# SCH_Tanbre_v2_2026-05-30_new.net
KiCad netlist of a schematic drawn in EasyEDA
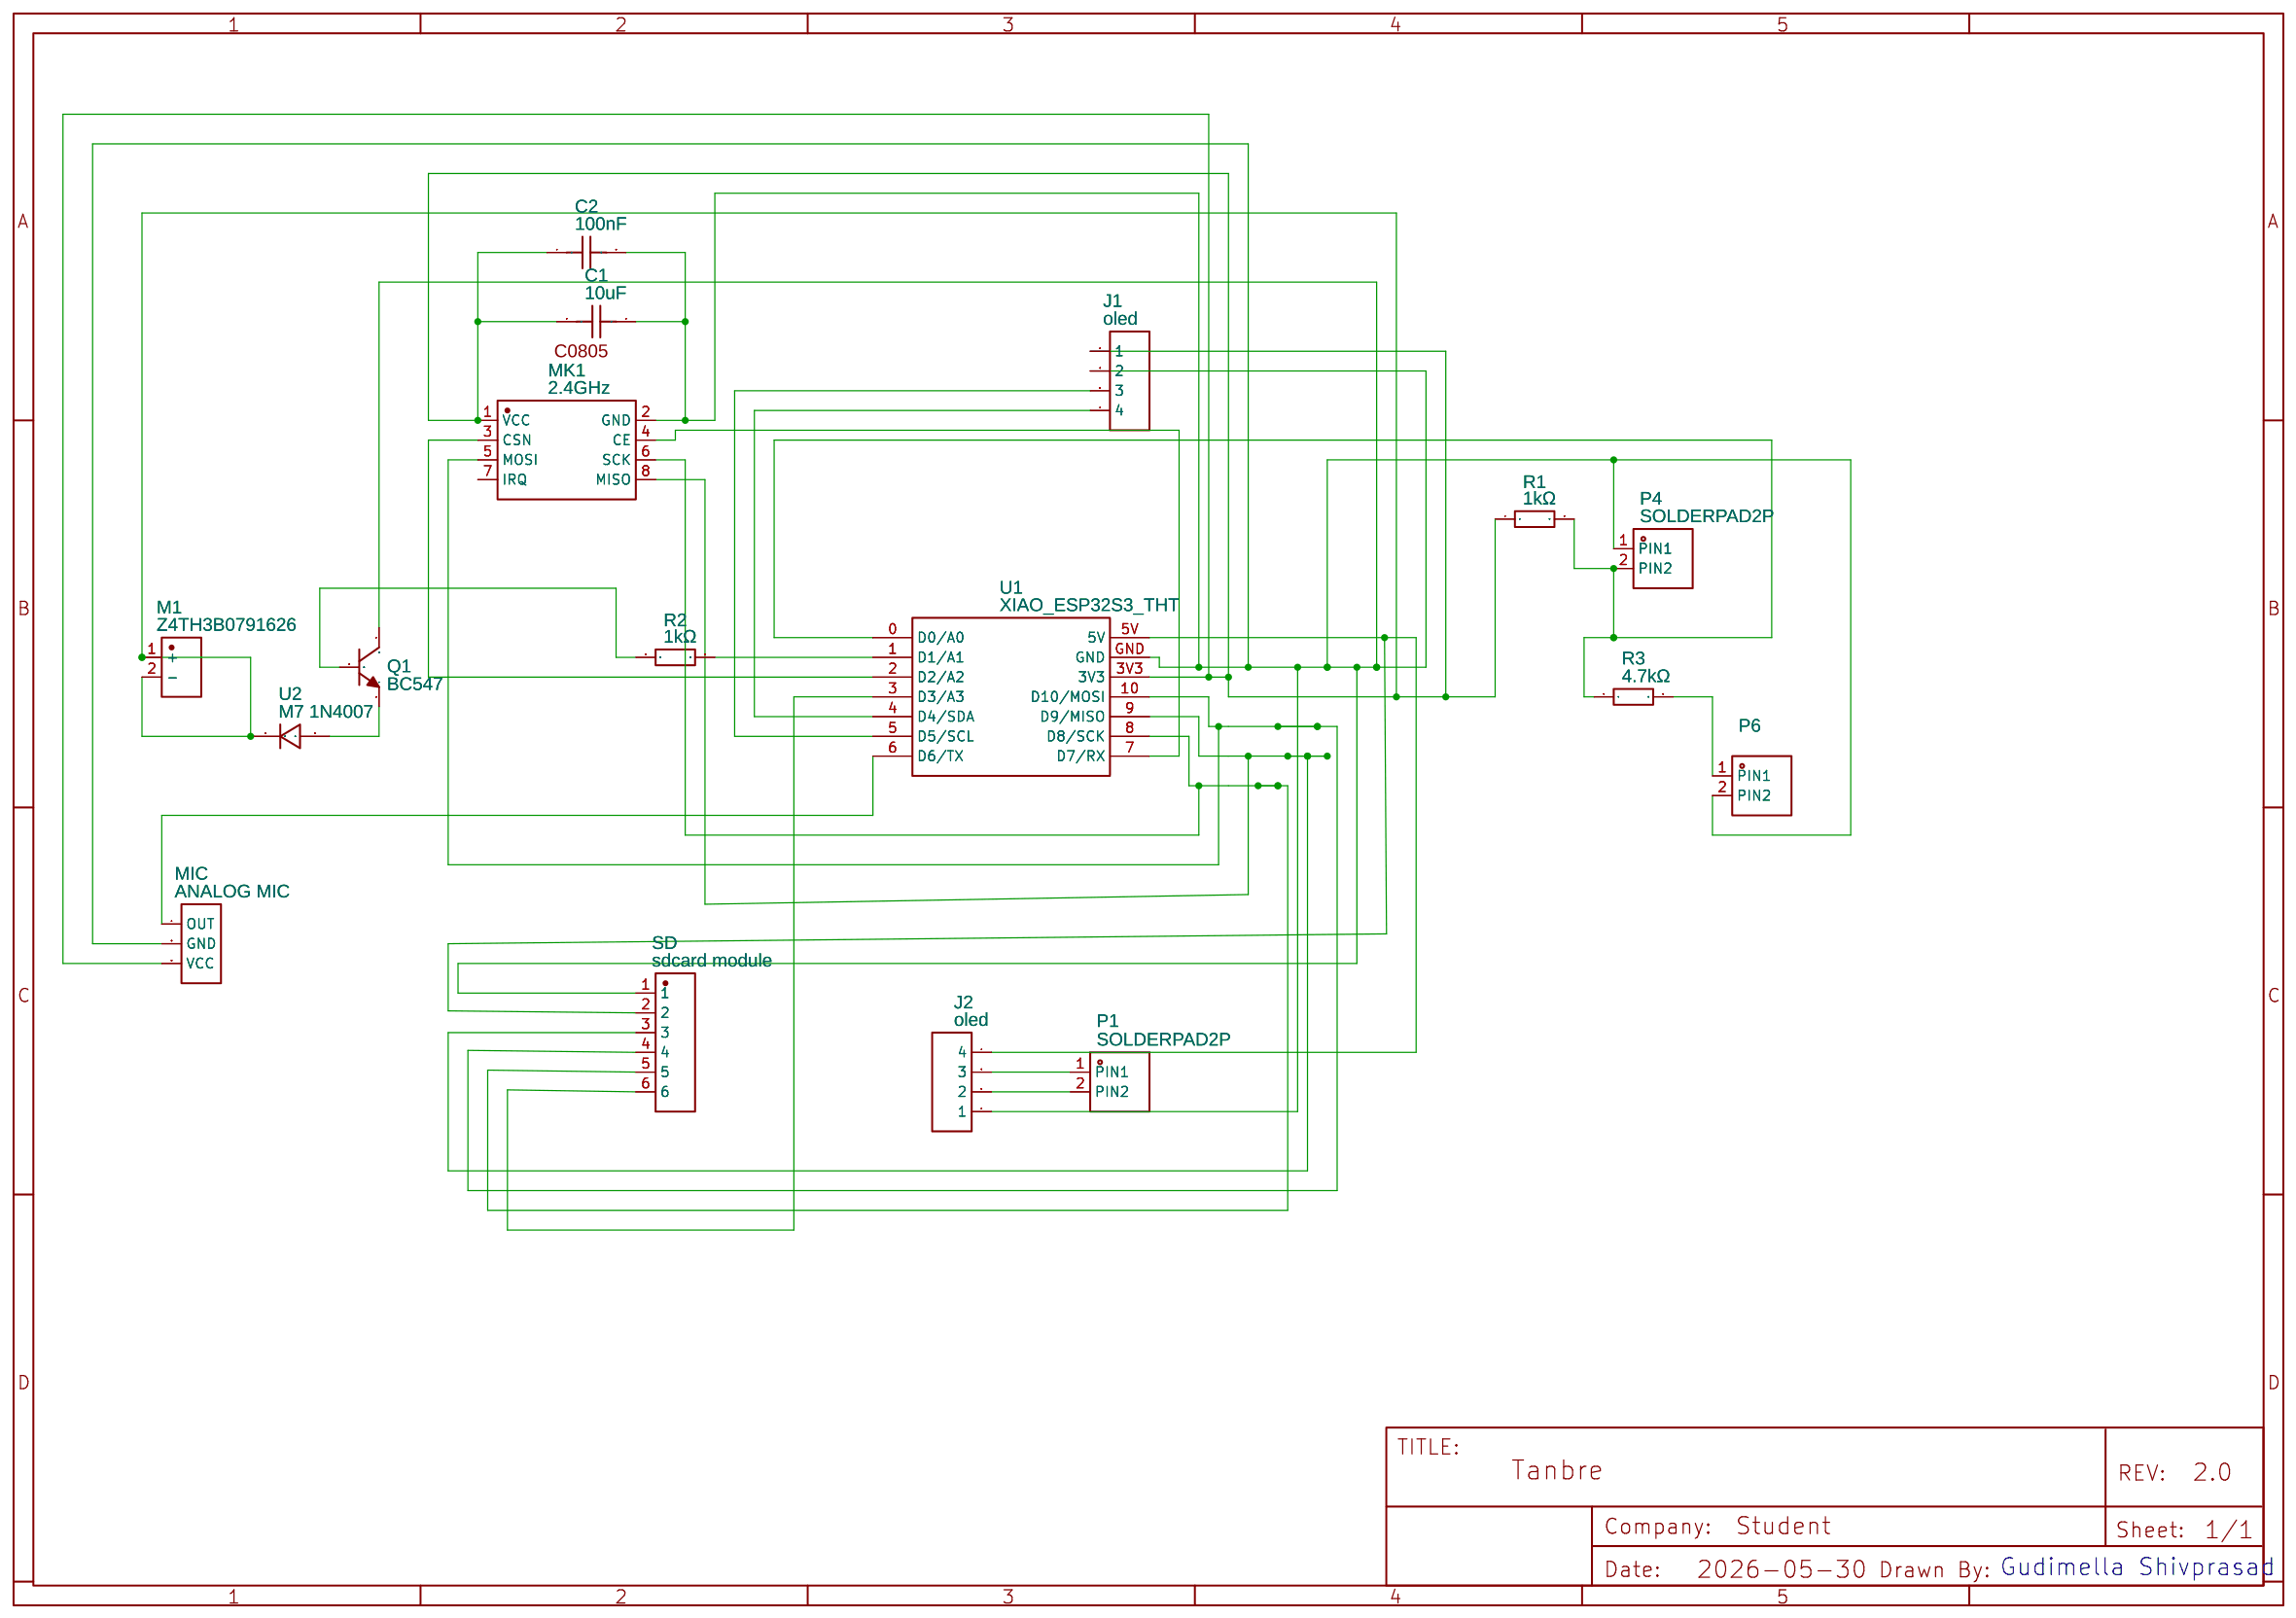
[diagram p0: schematic sheet]

(export (version "E")
  (design (tool "Eeschema 10.0.6"))
  (components
    (comp (ref "C1")
      (value "10uF")
      (fields
        (field (name "Manufacturer Part") "V106K0805X5R250NHP")
        (field (name "Manufacturer") "VIIYONG(微容)")
      )
      (libsource (lib "") (part "V106K0805X5R250NHP"))
    )
    (comp (ref "C2")
      (value "100nF")
      (fields
        (field (name "Manufacturer Part") "VJ0805Y104KXXCW1BC")
        (field (name "Manufacturer") "VISHAY(威世)")
      )
      (libsource (lib "") (part "VJ0805Y104KXXCW1BC"))
    )
    (comp (ref "J1") (value "oled") (libsource (lib "") (part "HDR-M-2.54_1x4")))
    (comp (ref "J2") (value "oled") (libsource (lib "") (part "HDR-M-2.54_1x4_1")))
    (comp (ref "M1")
      (value "Z4TH3B0791626")
      (fields (field (name "Manufacturer") "KOTL(金龙机电)"))
      (libsource (lib "") (part "Z4TH3B0791626"))
    )
    (comp (ref "MIC") (value "ANALOG MIC") (libsource (lib "") (part "HDR-M-2.54_1x3")))
    (comp (ref "MK1")
      (value "2.4GHz")
      (fields (field (name "Manufacturer Part") "NF-04") (field (name "Manufacturer") "Ai-Thinker(安信可)"))
      (libsource (lib "") (part "NRF24L01"))
    )
    (comp (ref "P1")
      (value "SOLDERPAD2P")
      (fields (field (name "Manufacturer Part") "New SchematicLib"))
      (libsource (lib "") (part "SOLDERPAD2P"))
    )
    (comp (ref "P4")
      (value "SOLDERPAD2P")
      (fields (field (name "Manufacturer Part") "New SchematicLib"))
      (libsource (lib "") (part "SOLDERPAD2P"))
    )
    (comp (ref "P6")
      (value "SOLDERPAD2P")
      (fields (field (name "Manufacturer Part") "New SchematicLib"))
      (libsource (lib "") (part "SOLDERPAD2P"))
    )
    (comp (ref "Q1")
      (value "BC547")
      (fields
        (field (name "Manufacturer Part") "BC547(RANGE:420-800)")
        (field (name "Manufacturer") "CJ(江苏长电/长晶)")
      )
      (libsource (lib "") (part "BC547"))
    )
    (comp (ref "R1")
      (value "1kΩ")
      (fields (field (name "Manufacturer Part") "CR-02JL6----1K") (field (name "Manufacturer") "Viking(光颉)"))
      (libsource (lib "") (part "CR-02JL6----1K"))
    )
    (comp (ref "R2")
      (value "1kΩ")
      (fields (field (name "Manufacturer Part") "CR-02JL6----1K") (field (name "Manufacturer") "Viking(光颉)"))
      (libsource (lib "") (part "CR-02JL6----1K"))
    )
    (comp (ref "R3")
      (value "4.7kΩ")
      (fields (field (name "Manufacturer Part") "RMC12064.7K5%N") (field (name "Manufacturer") "Tyohm(幸亚电阻)"))
      (libsource (lib "") (part "RMC12064.7K5%N"))
    )
    (comp (ref "SD")
      (value "sdcard module")
      (fields
        (field (name "Manufacturer Part") "HC-PM254-5.0H-1x6PZ")
        (field (name "Manufacturer") "HC(虹成电子)")
      )
      (libsource (lib "") (part "HC-PM254-5.0H-1X6PZ"))
    )
    (comp (ref "U1") (value "XIAO_ESP32S3_THT") (libsource (lib "") (part "XIAO_ESP32S3_THT")))
    (comp (ref "U2")
      (value "M7 1N4007")
      (fields (field (name "Manufacturer") "JUXING(钜兴)"))
      (libsource (lib "") (part "M7 1N4007"))
    )
  )
  (nets
    (net (code "1") (name "Net-(J2-Pad4)") (class "Default")
      (node (ref "J2") (pin "4") (pinfunction "4_4") (pintype "unspecified"))
      (node (ref "SD") (pin "2") (pinfunction "2_2") (pintype "unspecified"))
      (node (ref "U1") (pin "5V") (pinfunction "5V_5V") (pintype "unspecified"))
    )
    (net (code "2") (name "Net-(M1-+)") (class "Default")
      (node (ref "C1") (pin "1") (pinfunction "1_1") (pintype "unspecified"))
      (node (ref "C2") (pin "1") (pinfunction "1_1") (pintype "unspecified"))
      (node (ref "J1") (pin "1") (pinfunction "1_1") (pintype "unspecified"))
      (node (ref "M1") (pin "1") (pinfunction "+_1") (pintype "unspecified"))
      (node (ref "M1") (pin "2") (pinfunction "-_2") (pintype "unspecified"))
      (node (ref "MIC") (pin "3") (pinfunction "VCC_3") (pintype "unspecified"))
      (node (ref "MK1") (pin "1") (pinfunction "VCC_1") (pintype "unspecified"))
      (node (ref "R1") (pin "1") (pinfunction "1_1") (pintype "unspecified"))
      (node (ref "U1") (pin "3V3") (pinfunction "3V3_3V3") (pintype "unspecified"))
      (node (ref "U2") (pin "1") (pinfunction "1_1") (pintype "unspecified"))
    )
    (net (code "3") (name "Net-(MIC-GND)") (class "Default")
      (node (ref "C1") (pin "2") (pinfunction "2_2") (pintype "unspecified"))
      (node (ref "C2") (pin "2") (pinfunction "2_2") (pintype "unspecified"))
      (node (ref "J1") (pin "2") (pinfunction "2_2") (pintype "unspecified"))
      (node (ref "J2") (pin "1") (pinfunction "1_1") (pintype "unspecified"))
      (node (ref "MIC") (pin "2") (pinfunction "GND_2") (pintype "unspecified"))
      (node (ref "MK1") (pin "2") (pinfunction "GND_2") (pintype "unspecified"))
      (node (ref "P4") (pin "1") (pinfunction "PIN1_1") (pintype "unspecified"))
      (node (ref "P6") (pin "2") (pinfunction "PIN2_2") (pintype "unspecified"))
      (node (ref "Q1") (pin "1") (pinfunction "C_1") (pintype "unspecified"))
      (node (ref "SD") (pin "1") (pinfunction "1_1") (pintype "unspecified"))
      (node (ref "U1") (pin "GND") (pinfunction "GND_GND") (pintype "unspecified"))
    )
    (net (code "4") (name "Net-(MIC-OUT)") (class "Default")
      (node (ref "MIC") (pin "1") (pinfunction "OUT_1") (pintype "unspecified"))
      (node (ref "U1") (pin "6") (pinfunction "D6/TX_6") (pintype "unspecified"))
    )
    (net (code "5") (name "Net-(MK1-CE)") (class "Default")
      (node (ref "MK1") (pin "4") (pinfunction "CE_4") (pintype "unspecified"))
      (node (ref "U1") (pin "7") (pinfunction "D7/RX_7") (pintype "unspecified"))
    )
    (net (code "6") (name "Net-(MK1-CSN)") (class "Default")
      (node (ref "MK1") (pin "3") (pinfunction "CSN_3") (pintype "unspecified"))
      (node (ref "U1") (pin "2") (pinfunction "D2/A2_2") (pintype "unspecified"))
    )
    (net (code "7") (name "Net-(MK1-MISO)") (class "Default")
      (node (ref "MK1") (pin "8") (pinfunction "MISO_8") (pintype "unspecified"))
      (node (ref "SD") (pin "3") (pinfunction "3_3") (pintype "unspecified"))
      (node (ref "U1") (pin "9") (pinfunction "D9/MISO_9") (pintype "unspecified"))
    )
    (net (code "8") (name "Net-(MK1-MOSI)") (class "Default")
      (node (ref "MK1") (pin "5") (pinfunction "MOSI_5") (pintype "unspecified"))
      (node (ref "SD") (pin "4") (pinfunction "4_4") (pintype "unspecified"))
      (node (ref "U1") (pin "10") (pinfunction "D10/MOSI_10") (pintype "unspecified"))
    )
    (net (code "9") (name "Net-(MK1-SCK)") (class "Default")
      (node (ref "MK1") (pin "6") (pinfunction "SCK_6") (pintype "unspecified"))
      (node (ref "SD") (pin "5") (pinfunction "5_5") (pintype "unspecified"))
      (node (ref "U1") (pin "8") (pinfunction "D8/SCK_8") (pintype "unspecified"))
    )
    (net (code "10") (name "Net-(P1-PIN1)") (class "Default")
      (node (ref "J2") (pin "3") (pinfunction "3_3") (pintype "unspecified"))
      (node (ref "P1") (pin "1") (pinfunction "PIN1_1") (pintype "unspecified"))
    )
    (net (code "11") (name "Net-(P1-PIN2)") (class "Default")
      (node (ref "J2") (pin "2") (pinfunction "2_2") (pintype "unspecified"))
      (node (ref "P1") (pin "2") (pinfunction "PIN2_2") (pintype "unspecified"))
    )
    (net (code "12") (name "Net-(P4-PIN2)") (class "Default")
      (node (ref "P4") (pin "2") (pinfunction "PIN2_2") (pintype "unspecified"))
      (node (ref "R1") (pin "2") (pinfunction "2_2") (pintype "unspecified"))
      (node (ref "R3") (pin "1") (pinfunction "1_1") (pintype "unspecified"))
      (node (ref "U1") (pin "0") (pinfunction "D0/A0_0") (pintype "unspecified"))
    )
    (net (code "13") (name "Net-(P6-PIN1)") (class "Default")
      (node (ref "P6") (pin "1") (pinfunction "PIN1_1") (pintype "unspecified"))
      (node (ref "R3") (pin "2") (pinfunction "2_2") (pintype "unspecified"))
    )
    (net (code "14") (name "Net-(Q1-B)") (class "Default")
      (node (ref "Q1") (pin "2") (pinfunction "B_2") (pintype "unspecified"))
      (node (ref "R2") (pin "1") (pinfunction "1_1") (pintype "unspecified"))
    )
    (net (code "15") (name "Net-(Q1-E)") (class "Default")
      (node (ref "Q1") (pin "3") (pinfunction "E_3") (pintype "unspecified"))
      (node (ref "U2") (pin "2") (pinfunction "2_2") (pintype "unspecified"))
    )
    (net (code "16") (name "Net-(U1-D1{slash}A1)") (class "Default")
      (node (ref "R2") (pin "2") (pinfunction "2_2") (pintype "unspecified"))
      (node (ref "U1") (pin "1") (pinfunction "D1/A1_1") (pintype "unspecified"))
    )
    (net (code "17") (name "Net-(U1-D3{slash}A3)") (class "Default")
      (node (ref "SD") (pin "6") (pinfunction "6_6") (pintype "unspecified"))
      (node (ref "U1") (pin "3") (pinfunction "D3/A3_3") (pintype "unspecified"))
    )
    (net (code "18") (name "Net-(U1-D4{slash}SDA)") (class "Default")
      (node (ref "J1") (pin "4") (pinfunction "4_4") (pintype "unspecified"))
      (node (ref "U1") (pin "4") (pinfunction "D4/SDA_4") (pintype "unspecified"))
    )
    (net (code "19") (name "Net-(U1-D5{slash}SCL)") (class "Default")
      (node (ref "J1") (pin "3") (pinfunction "3_3") (pintype "unspecified"))
      (node (ref "U1") (pin "5") (pinfunction "D5/SCL_5") (pintype "unspecified"))
    )
    (net (code "20") (name "unconnected-(MK1-IRQ-Pad7)") (class "Default")
      (node (ref "MK1") (pin "7") (pinfunction "IRQ_7") (pintype "unspecified"))
    )
  )
)
